# Mega_Relay_Interface.net
KiCad netlist of a schematic drawn in EAGLE
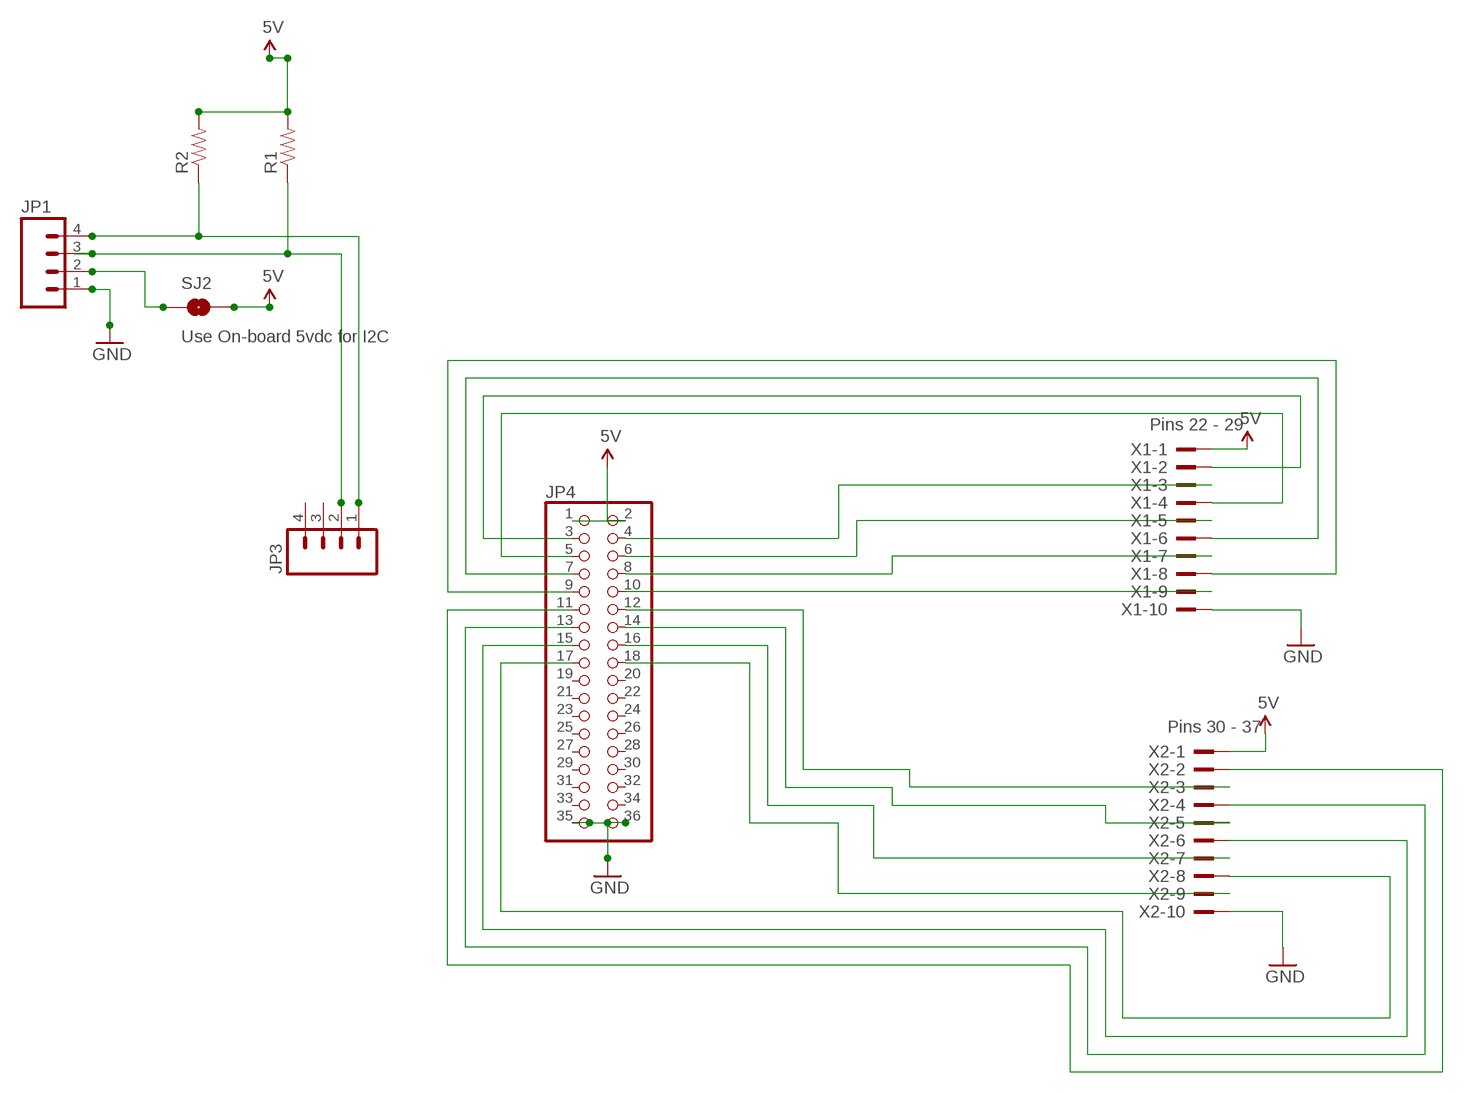
[diagram p0: schematic, sheet 1]

(export (version "E")
  (design (tool "Eeschema 10.0.6"))
  (components
    (comp (ref "JP1")
      (value "M04PTH")
      (footprint "eagle-import:1X04")
      (libsource (lib "eagle-import") (part "M04PTH"))
    )
    (comp (ref "JP3")
      (value "M04PTH")
      (footprint "eagle-import:1X04")
      (libsource (lib "eagle-import") (part "M04PTH"))
    )
    (comp (ref "JP4")
      (value "PINHD-2X18")
      (footprint "eagle-import:2X18")
      (libsource (lib "eagle-import") (part "PINHD-2X18"))
    )
    (comp (ref "R1")
      (value "RESISTORAXIAL-0.3")
      (footprint "eagle-import:AXIAL-0.3")
      (libsource (lib "eagle-import") (part "RESISTORAXIAL-0.3"))
    )
    (comp (ref "R2")
      (value "RESISTORAXIAL-0.3")
      (footprint "eagle-import:AXIAL-0.3")
      (libsource (lib "eagle-import") (part "RESISTORAXIAL-0.3"))
    )
    (comp (ref "SJ2")
      (value "Use On-board 5vdc for I2C")
      (footprint "eagle-import:SJ_2S")
      (libsource (lib "eagle-import") (part "SOLDERJUMPERNC"))
    )
    (comp (ref "X1")
      (value "Pins 22 - 29")
      (footprint "eagle-import:PAK100_2500-10")
      (fields (field (name "MF") "3M") (field (name "MPN") "2510-6002UB"))
      (libsource (lib "eagle-import") (part "2510-"))
    )
    (comp (ref "X2")
      (value "Pins 30 - 37")
      (footprint "eagle-import:PAK100_2500-10")
      (fields (field (name "MF") "3M") (field (name "MPN") "2510-6002UB"))
      (libsource (lib "eagle-import") (part "2510-"))
    )
  )
  (nets
    (net (code "1") (name "5V") (class "Default")
      (node (ref "JP4") (pin "1") (pinfunction "1_1") (pintype "passive"))
      (node (ref "JP4") (pin "2") (pinfunction "2_2") (pintype "passive"))
      (node (ref "R1") (pin "P$2") (pinfunction "2_P$2") (pintype "passive"))
      (node (ref "R2") (pin "P$2") (pinfunction "2_P$2") (pintype "passive"))
      (node (ref "SJ2") (pin "2") (pinfunction "2_2") (pintype "passive"))
      (node (ref "X1") (pin "1") (pinfunction "KL_1") (pintype "passive"))
      (node (ref "X2") (pin "1") (pinfunction "KL_1") (pintype "passive"))
    )
    (net (code "2") (name "GND") (class "Default")
      (node (ref "JP1") (pin "1") (pinfunction "1_1") (pintype "passive"))
      (node (ref "JP4") (pin "35") (pinfunction "35_35") (pintype "passive"))
      (node (ref "JP4") (pin "36") (pinfunction "36_36") (pintype "passive"))
      (node (ref "X1") (pin "10") (pinfunction "KL_10") (pintype "passive"))
      (node (ref "X2") (pin "10") (pinfunction "KL_10") (pintype "passive"))
    )
    (net (code "3") (name "Net-(JP1-Pad2)") (class "Default")
      (node (ref "JP1") (pin "2") (pinfunction "2_2") (pintype "passive"))
      (node (ref "SJ2") (pin "1") (pinfunction "1_1") (pintype "passive"))
    )
    (net (code "4") (name "Net-(R1-1)") (class "Default")
      (node (ref "JP1") (pin "3") (pinfunction "3_3") (pintype "passive"))
      (node (ref "JP3") (pin "2") (pinfunction "2_2") (pintype "passive"))
      (node (ref "R1") (pin "P$1") (pinfunction "1_P$1") (pintype "passive"))
    )
    (net (code "5") (name "Net-(R2-1)") (class "Default")
      (node (ref "JP1") (pin "4") (pinfunction "4_4") (pintype "passive"))
      (node (ref "JP3") (pin "1") (pinfunction "1_1") (pintype "passive"))
      (node (ref "R2") (pin "P$1") (pinfunction "1_P$1") (pintype "passive"))
    )
    (net (code "6") (name "Net-(X1C-KL)") (class "Default")
      (node (ref "JP4") (pin "3") (pinfunction "3_3") (pintype "passive"))
      (node (ref "X1") (pin "2") (pinfunction "KL_2") (pintype "passive"))
    )
    (net (code "7") (name "Net-(X1D-KL)") (class "Default")
      (node (ref "JP4") (pin "4") (pinfunction "4_4") (pintype "passive"))
      (node (ref "X1") (pin "3") (pinfunction "KL_3") (pintype "passive"))
    )
    (net (code "8") (name "Net-(X1E-KL)") (class "Default")
      (node (ref "JP4") (pin "5") (pinfunction "5_5") (pintype "passive"))
      (node (ref "X1") (pin "4") (pinfunction "KL_4") (pintype "passive"))
    )
    (net (code "9") (name "Net-(X1F-KL)") (class "Default")
      (node (ref "JP4") (pin "6") (pinfunction "6_6") (pintype "passive"))
      (node (ref "X1") (pin "5") (pinfunction "KL_5") (pintype "passive"))
    )
    (net (code "10") (name "Net-(X1G-KL)") (class "Default")
      (node (ref "JP4") (pin "7") (pinfunction "7_7") (pintype "passive"))
      (node (ref "X1") (pin "6") (pinfunction "KL_6") (pintype "passive"))
    )
    (net (code "11") (name "Net-(X1H-KL)") (class "Default")
      (node (ref "JP4") (pin "8") (pinfunction "8_8") (pintype "passive"))
      (node (ref "X1") (pin "7") (pinfunction "KL_7") (pintype "passive"))
    )
    (net (code "12") (name "Net-(X1I-KL)") (class "Default")
      (node (ref "JP4") (pin "9") (pinfunction "9_9") (pintype "passive"))
      (node (ref "X1") (pin "8") (pinfunction "KL_8") (pintype "passive"))
    )
    (net (code "13") (name "Net-(X1J-KL)") (class "Default")
      (node (ref "JP4") (pin "10") (pinfunction "10_10") (pintype "passive"))
      (node (ref "X1") (pin "9") (pinfunction "KL_9") (pintype "passive"))
    )
    (net (code "14") (name "Net-(X2C-KL)") (class "Default")
      (node (ref "JP4") (pin "11") (pinfunction "11_11") (pintype "passive"))
      (node (ref "X2") (pin "2") (pinfunction "KL_2") (pintype "passive"))
    )
    (net (code "15") (name "Net-(X2D-KL)") (class "Default")
      (node (ref "JP4") (pin "12") (pinfunction "12_12") (pintype "passive"))
      (node (ref "X2") (pin "3") (pinfunction "KL_3") (pintype "passive"))
    )
    (net (code "16") (name "Net-(X2E-KL)") (class "Default")
      (node (ref "JP4") (pin "13") (pinfunction "13_13") (pintype "passive"))
      (node (ref "X2") (pin "4") (pinfunction "KL_4") (pintype "passive"))
    )
    (net (code "17") (name "Net-(X2F-KL)") (class "Default")
      (node (ref "JP4") (pin "14") (pinfunction "14_14") (pintype "passive"))
      (node (ref "X2") (pin "5") (pinfunction "KL_5") (pintype "passive"))
    )
    (net (code "18") (name "Net-(X2G-KL)") (class "Default")
      (node (ref "JP4") (pin "15") (pinfunction "15_15") (pintype "passive"))
      (node (ref "X2") (pin "6") (pinfunction "KL_6") (pintype "passive"))
    )
    (net (code "19") (name "Net-(X2H-KL)") (class "Default")
      (node (ref "JP4") (pin "16") (pinfunction "16_16") (pintype "passive"))
      (node (ref "X2") (pin "7") (pinfunction "KL_7") (pintype "passive"))
    )
    (net (code "20") (name "Net-(X2I-KL)") (class "Default")
      (node (ref "JP4") (pin "17") (pinfunction "17_17") (pintype "passive"))
      (node (ref "X2") (pin "8") (pinfunction "KL_8") (pintype "passive"))
    )
    (net (code "21") (name "Net-(X2J-KL)") (class "Default")
      (node (ref "JP4") (pin "18") (pinfunction "18_18") (pintype "passive"))
      (node (ref "X2") (pin "9") (pinfunction "KL_9") (pintype "passive"))
    )
    (net (code "22") (name "unconnected-(JP3-Pad3)") (class "Default")
      (node (ref "JP3") (pin "3") (pinfunction "3_3") (pintype "passive"))
    )
    (net (code "23") (name "unconnected-(JP3-Pad4)") (class "Default")
      (node (ref "JP3") (pin "4") (pinfunction "4_4") (pintype "passive"))
    )
    (net (code "24") (name "unconnected-(JP4-Pad19)") (class "Default")
      (node (ref "JP4") (pin "19") (pinfunction "19_19") (pintype "passive"))
    )
    (net (code "25") (name "unconnected-(JP4-Pad20)") (class "Default")
      (node (ref "JP4") (pin "20") (pinfunction "20_20") (pintype "passive"))
    )
    (net (code "26") (name "unconnected-(JP4-Pad21)") (class "Default")
      (node (ref "JP4") (pin "21") (pinfunction "21_21") (pintype "passive"))
    )
    (net (code "27") (name "unconnected-(JP4-Pad22)") (class "Default")
      (node (ref "JP4") (pin "22") (pinfunction "22_22") (pintype "passive"))
    )
    (net (code "28") (name "unconnected-(JP4-Pad23)") (class "Default")
      (node (ref "JP4") (pin "23") (pinfunction "23_23") (pintype "passive"))
    )
    (net (code "29") (name "unconnected-(JP4-Pad24)") (class "Default")
      (node (ref "JP4") (pin "24") (pinfunction "24_24") (pintype "passive"))
    )
    (net (code "30") (name "unconnected-(JP4-Pad25)") (class "Default")
      (node (ref "JP4") (pin "25") (pinfunction "25_25") (pintype "passive"))
    )
    (net (code "31") (name "unconnected-(JP4-Pad26)") (class "Default")
      (node (ref "JP4") (pin "26") (pinfunction "26_26") (pintype "passive"))
    )
    (net (code "32") (name "unconnected-(JP4-Pad27)") (class "Default")
      (node (ref "JP4") (pin "27") (pinfunction "27_27") (pintype "passive"))
    )
    (net (code "33") (name "unconnected-(JP4-Pad28)") (class "Default")
      (node (ref "JP4") (pin "28") (pinfunction "28_28") (pintype "passive"))
    )
    (net (code "34") (name "unconnected-(JP4-Pad29)") (class "Default")
      (node (ref "JP4") (pin "29") (pinfunction "29_29") (pintype "passive"))
    )
    (net (code "35") (name "unconnected-(JP4-Pad30)") (class "Default")
      (node (ref "JP4") (pin "30") (pinfunction "30_30") (pintype "passive"))
    )
    (net (code "36") (name "unconnected-(JP4-Pad31)") (class "Default")
      (node (ref "JP4") (pin "31") (pinfunction "31_31") (pintype "passive"))
    )
    (net (code "37") (name "unconnected-(JP4-Pad32)") (class "Default")
      (node (ref "JP4") (pin "32") (pinfunction "32_32") (pintype "passive"))
    )
    (net (code "38") (name "unconnected-(JP4-Pad33)") (class "Default")
      (node (ref "JP4") (pin "33") (pinfunction "33_33") (pintype "passive"))
    )
    (net (code "39") (name "unconnected-(JP4-Pad34)") (class "Default")
      (node (ref "JP4") (pin "34") (pinfunction "34_34") (pintype "passive"))
    )
  )
)
